# New_Project.net
KiCad netlist of a schematic drawn in EasyEDA
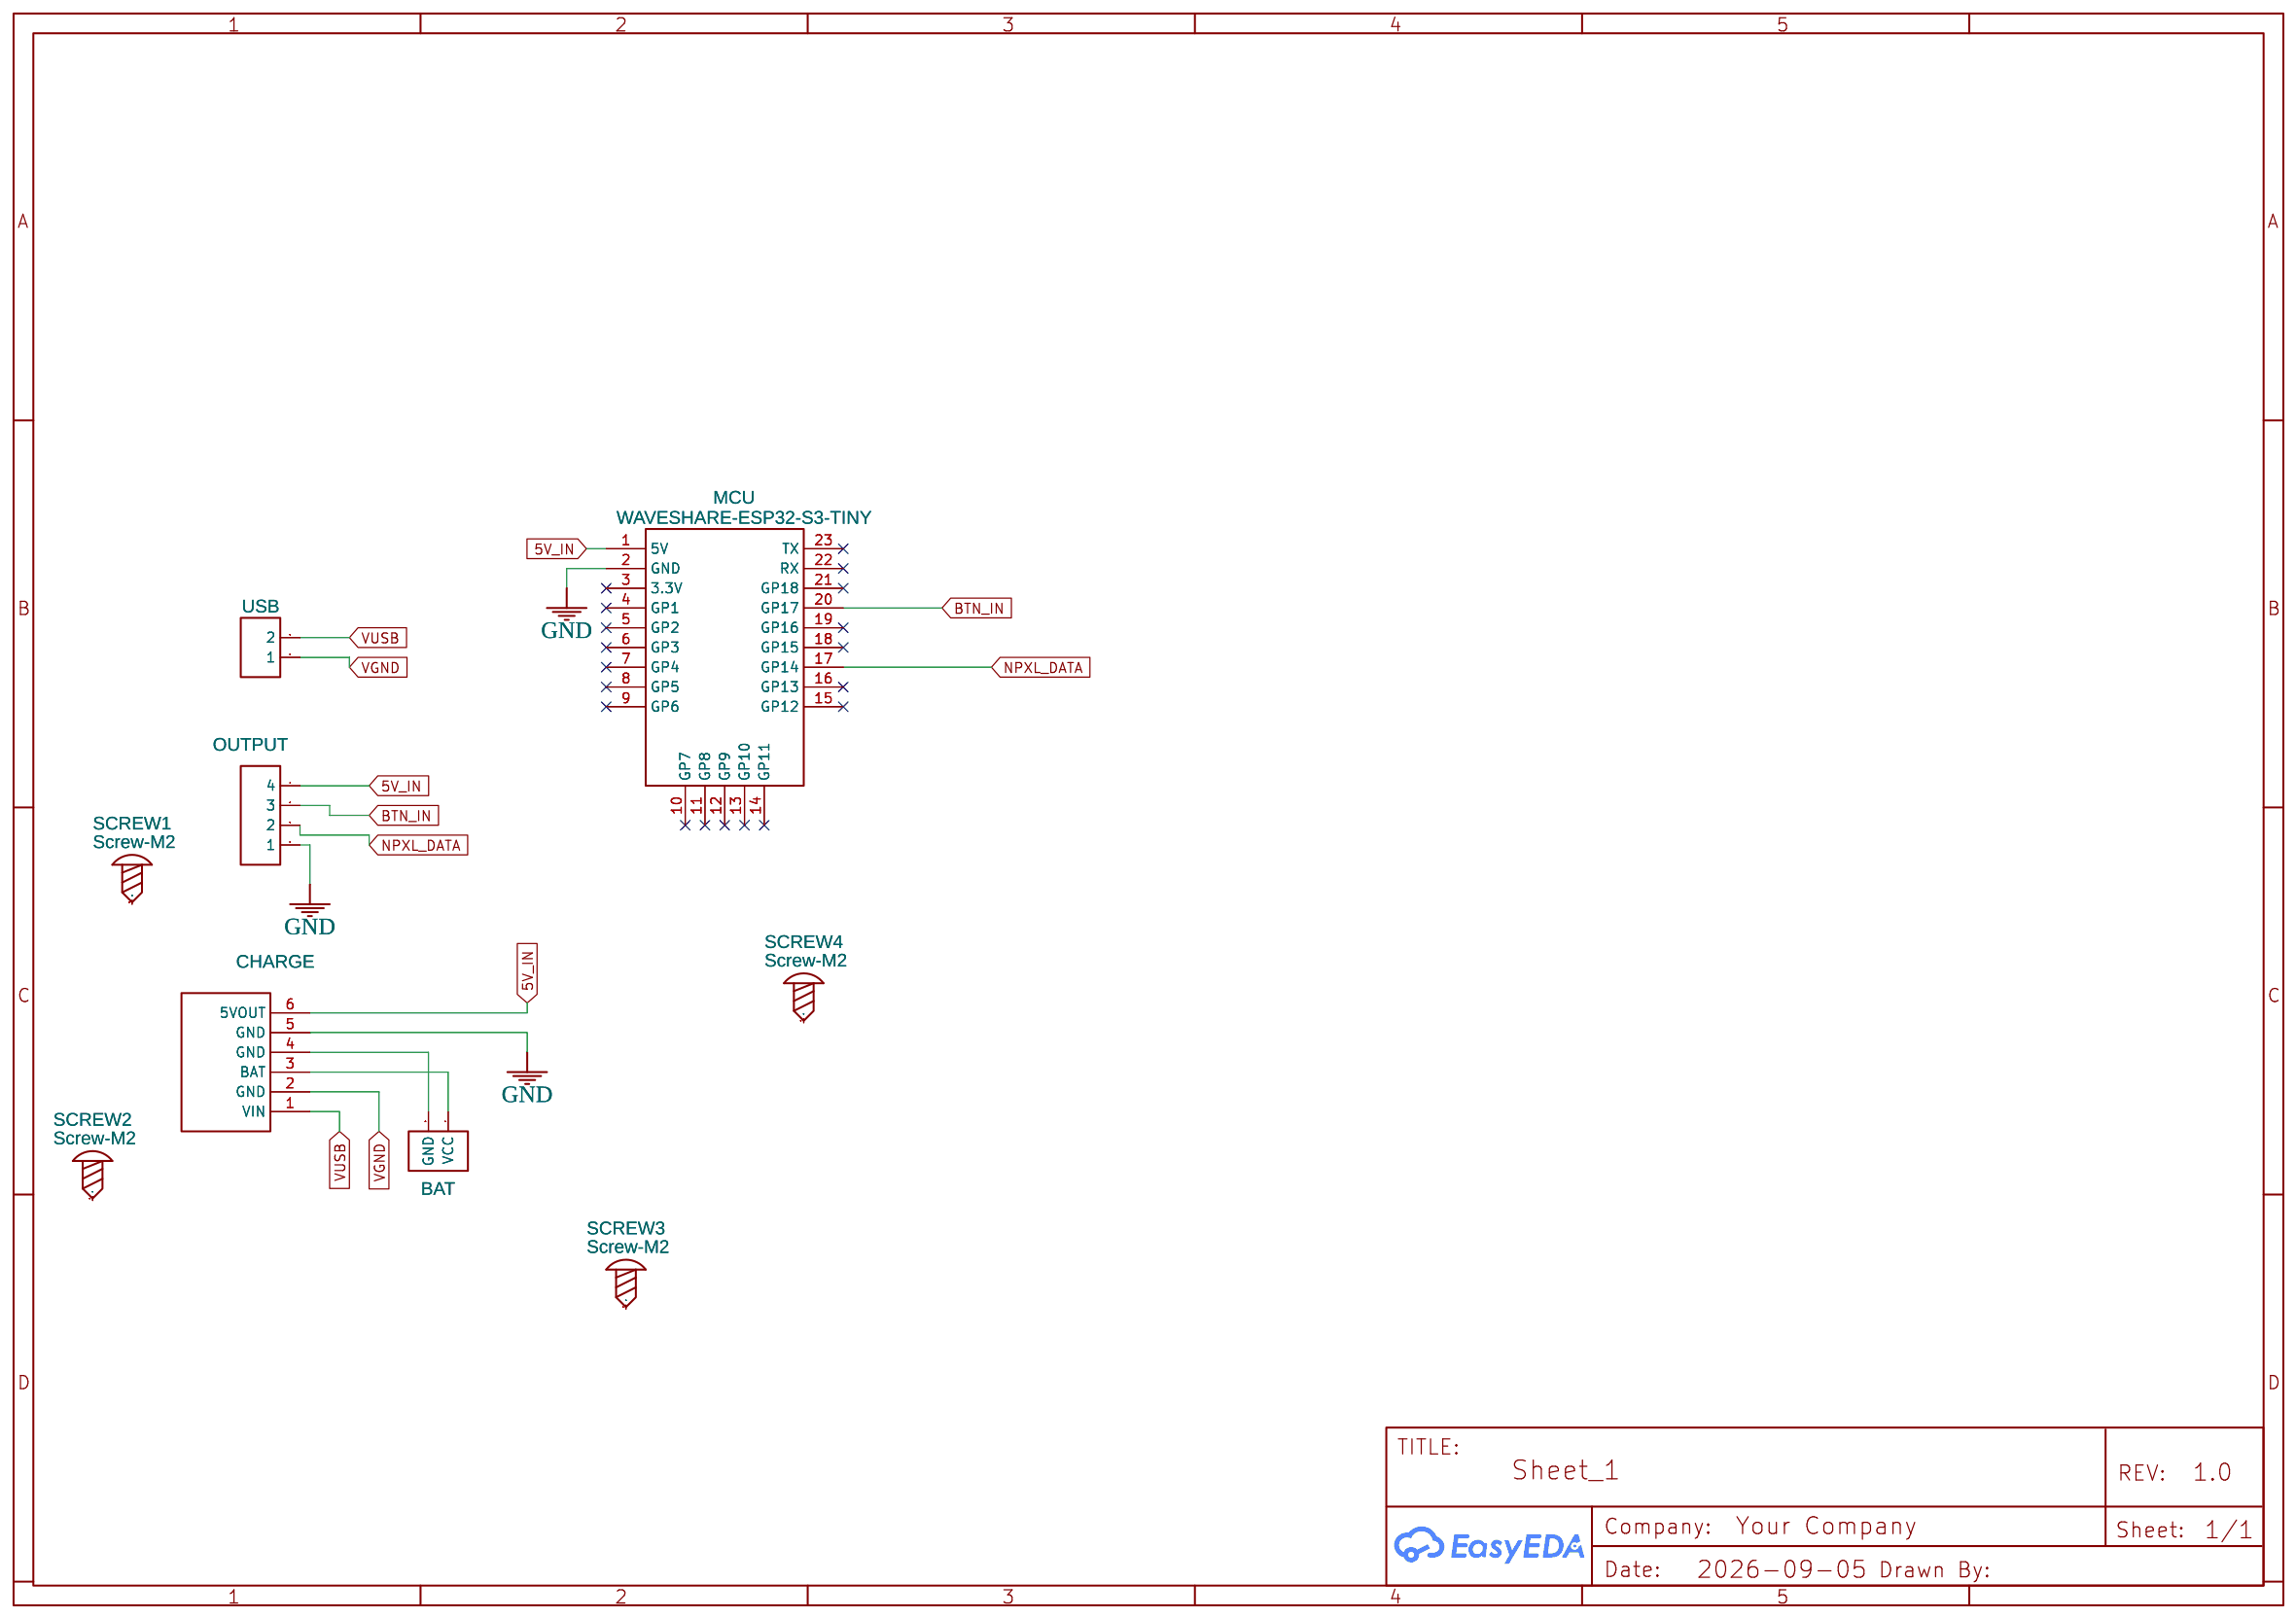
[diagram p0: schematic sheet]

(export (version "E")
  (design (tool "Eeschema 10.0.6"))
  (components
    (comp (ref "BAT") (value "Input") (libsource (lib "") (part "HDR-F-2.54_1x2")))
    (comp (ref "CHARGE")
      (value "2A_5V_CHARGE_DISCHARGE_INTEGRATED_3.7V_4.2V_LITHIUM_BATTERY_BOOST_WASN")
      (fields
        (field (name "Manufacturer Part") "2A_5V_Charge_Discharge_Integrated_3.7V_4.2V_Lithium_Battery_Boost_Mobile")
      )
      (libsource (lib "") (part "2A_5V_CHARGE_DISCHARGE_INTEGRATED_3.7V_4.2V_LITHIUM_BATTERY_BOOST_WASN"))
    )
    (comp (ref "MCU")
      (value "WAVESHARE-ESP32-S3-TINY")
      (fields
        (field (name "Manufacturer Part") "ESP32-S3 Mini Development Board")
        (field (name "Manufacturer") "WAVESHARE")
      )
      (libsource (lib "") (part "WAVESHARE-ESP32-S3-TINY"))
    )
    (comp (ref "OUTPUT") (value "output") (libsource (lib "") (part "HDR-F-2.54_1x4")))
    (comp (ref "SCREW1") (value "Screw-M2") (libsource (lib "") (part "Screw-M2")))
    (comp (ref "SCREW2") (value "Screw-M2") (libsource (lib "") (part "Screw-M2")))
    (comp (ref "SCREW3") (value "Screw-M2") (libsource (lib "") (part "Screw-M2")))
    (comp (ref "SCREW4") (value "Screw-M2") (libsource (lib "") (part "Screw-M2")))
    (comp (ref "USB") (value "HDR-M-2.54_1x2") (libsource (lib "") (part "HDR-M-2.54_1x2")))
  )
  (nets
    (net (code "1") (name "5V_IN") (class "Default")
      (node (ref "CHARGE") (pin "6") (pinfunction "5VOUT_6") (pintype "unspecified"))
      (node (ref "MCU") (pin "1") (pinfunction "5V_1") (pintype "unspecified"))
      (node (ref "OUTPUT") (pin "4") (pinfunction "4_4") (pintype "unspecified"))
    )
    (net (code "2") (name "BTN_IN") (class "Default")
      (node (ref "MCU") (pin "20") (pinfunction "GP17_20") (pintype "unspecified"))
      (node (ref "OUTPUT") (pin "3") (pinfunction "3_3") (pintype "unspecified"))
    )
    (net (code "3") (name "GND") (class "Default")
      (node (ref "CHARGE") (pin "5") (pinfunction "GND_5") (pintype "unspecified"))
      (node (ref "MCU") (pin "2") (pinfunction "GND_2") (pintype "unspecified"))
      (node (ref "OUTPUT") (pin "1") (pinfunction "1_1") (pintype "unspecified"))
    )
    (net (code "4") (name "NPXL_DATA") (class "Default")
      (node (ref "MCU") (pin "17") (pinfunction "GP14_17") (pintype "unspecified"))
      (node (ref "OUTPUT") (pin "2") (pinfunction "2_2") (pintype "unspecified"))
    )
    (net (code "5") (name "Net-(BAT-GND)") (class "Default")
      (node (ref "BAT") (pin "2") (pinfunction "GND_2") (pintype "input"))
      (node (ref "CHARGE") (pin "4") (pinfunction "GND_4") (pintype "unspecified"))
    )
    (net (code "6") (name "Net-(BAT-VCC)") (class "Default")
      (node (ref "BAT") (pin "1") (pinfunction "VCC_1") (pintype "input"))
      (node (ref "CHARGE") (pin "3") (pinfunction "BAT_3") (pintype "unspecified"))
    )
    (net (code "7") (name "VGND") (class "Default")
      (node (ref "CHARGE") (pin "2") (pinfunction "GND_2") (pintype "unspecified"))
      (node (ref "USB") (pin "1") (pinfunction "1_1") (pintype "unspecified"))
    )
    (net (code "8") (name "VUSB") (class "Default")
      (node (ref "CHARGE") (pin "1") (pinfunction "VIN_1") (pintype "unspecified"))
      (node (ref "USB") (pin "2") (pinfunction "2_2") (pintype "unspecified"))
    )
    (net (code "9") (name "unconnected-(MCU-3.3V-Pad3)") (class "Default")
      (node (ref "MCU") (pin "3") (pinfunction "3.3V_3") (pintype "unspecified+no_connect"))
    )
    (net (code "10") (name "unconnected-(MCU-GP1-Pad4)") (class "Default")
      (node (ref "MCU") (pin "4") (pinfunction "GP1_4") (pintype "unspecified+no_connect"))
    )
    (net (code "11") (name "unconnected-(MCU-GP2-Pad5)") (class "Default")
      (node (ref "MCU") (pin "5") (pinfunction "GP2_5") (pintype "unspecified+no_connect"))
    )
    (net (code "12") (name "unconnected-(MCU-GP3-Pad6)") (class "Default")
      (node (ref "MCU") (pin "6") (pinfunction "GP3_6") (pintype "unspecified+no_connect"))
    )
    (net (code "13") (name "unconnected-(MCU-GP4-Pad7)") (class "Default")
      (node (ref "MCU") (pin "7") (pinfunction "GP4_7") (pintype "unspecified+no_connect"))
    )
    (net (code "14") (name "unconnected-(MCU-GP5-Pad8)") (class "Default")
      (node (ref "MCU") (pin "8") (pinfunction "GP5_8") (pintype "unspecified+no_connect"))
    )
    (net (code "15") (name "unconnected-(MCU-GP6-Pad9)") (class "Default")
      (node (ref "MCU") (pin "9") (pinfunction "GP6_9") (pintype "unspecified+no_connect"))
    )
    (net (code "16") (name "unconnected-(MCU-GP7-Pad10)") (class "Default")
      (node (ref "MCU") (pin "10") (pinfunction "GP7_10") (pintype "unspecified+no_connect"))
    )
    (net (code "17") (name "unconnected-(MCU-GP8-Pad11)") (class "Default")
      (node (ref "MCU") (pin "11") (pinfunction "GP8_11") (pintype "unspecified+no_connect"))
    )
    (net (code "18") (name "unconnected-(MCU-GP9-Pad12)") (class "Default")
      (node (ref "MCU") (pin "12") (pinfunction "GP9_12") (pintype "unspecified+no_connect"))
    )
    (net (code "19") (name "unconnected-(MCU-GP10-Pad13)") (class "Default")
      (node (ref "MCU") (pin "13") (pinfunction "GP10_13") (pintype "unspecified+no_connect"))
    )
    (net (code "20") (name "unconnected-(MCU-GP11-Pad14)") (class "Default")
      (node (ref "MCU") (pin "14") (pinfunction "GP11_14") (pintype "unspecified+no_connect"))
    )
    (net (code "21") (name "unconnected-(MCU-GP12-Pad15)") (class "Default")
      (node (ref "MCU") (pin "15") (pinfunction "GP12_15") (pintype "unspecified+no_connect"))
    )
    (net (code "22") (name "unconnected-(MCU-GP13-Pad16)") (class "Default")
      (node (ref "MCU") (pin "16") (pinfunction "GP13_16") (pintype "unspecified+no_connect"))
    )
    (net (code "23") (name "unconnected-(MCU-GP15-Pad18)") (class "Default")
      (node (ref "MCU") (pin "18") (pinfunction "GP15_18") (pintype "unspecified+no_connect"))
    )
    (net (code "24") (name "unconnected-(MCU-GP16-Pad19)") (class "Default")
      (node (ref "MCU") (pin "19") (pinfunction "GP16_19") (pintype "unspecified+no_connect"))
    )
    (net (code "25") (name "unconnected-(MCU-GP18-Pad21)") (class "Default")
      (node (ref "MCU") (pin "21") (pinfunction "GP18_21") (pintype "unspecified+no_connect"))
    )
    (net (code "26") (name "unconnected-(MCU-RX-Pad22)") (class "Default")
      (node (ref "MCU") (pin "22") (pinfunction "RX_22") (pintype "unspecified+no_connect"))
    )
    (net (code "27") (name "unconnected-(MCU-TX-Pad23)") (class "Default")
      (node (ref "MCU") (pin "23") (pinfunction "TX_23") (pintype "unspecified+no_connect"))
    )
    (net (code "28") (name "unconnected-(SCREW1-Pad1)") (class "Default")
      (node (ref "SCREW1") (pin "1") (pinfunction "1_1") (pintype "unspecified"))
    )
    (net (code "29") (name "unconnected-(SCREW2-Pad1)") (class "Default")
      (node (ref "SCREW2") (pin "1") (pinfunction "1_1") (pintype "unspecified"))
    )
    (net (code "30") (name "unconnected-(SCREW3-Pad1)") (class "Default")
      (node (ref "SCREW3") (pin "1") (pinfunction "1_1") (pintype "unspecified"))
    )
    (net (code "31") (name "unconnected-(SCREW4-Pad1)") (class "Default")
      (node (ref "SCREW4") (pin "1") (pinfunction "1_1") (pintype "unspecified"))
    )
  )
)
